# motor_node.net
KiCad netlist of a schematic drawn in EAGLE
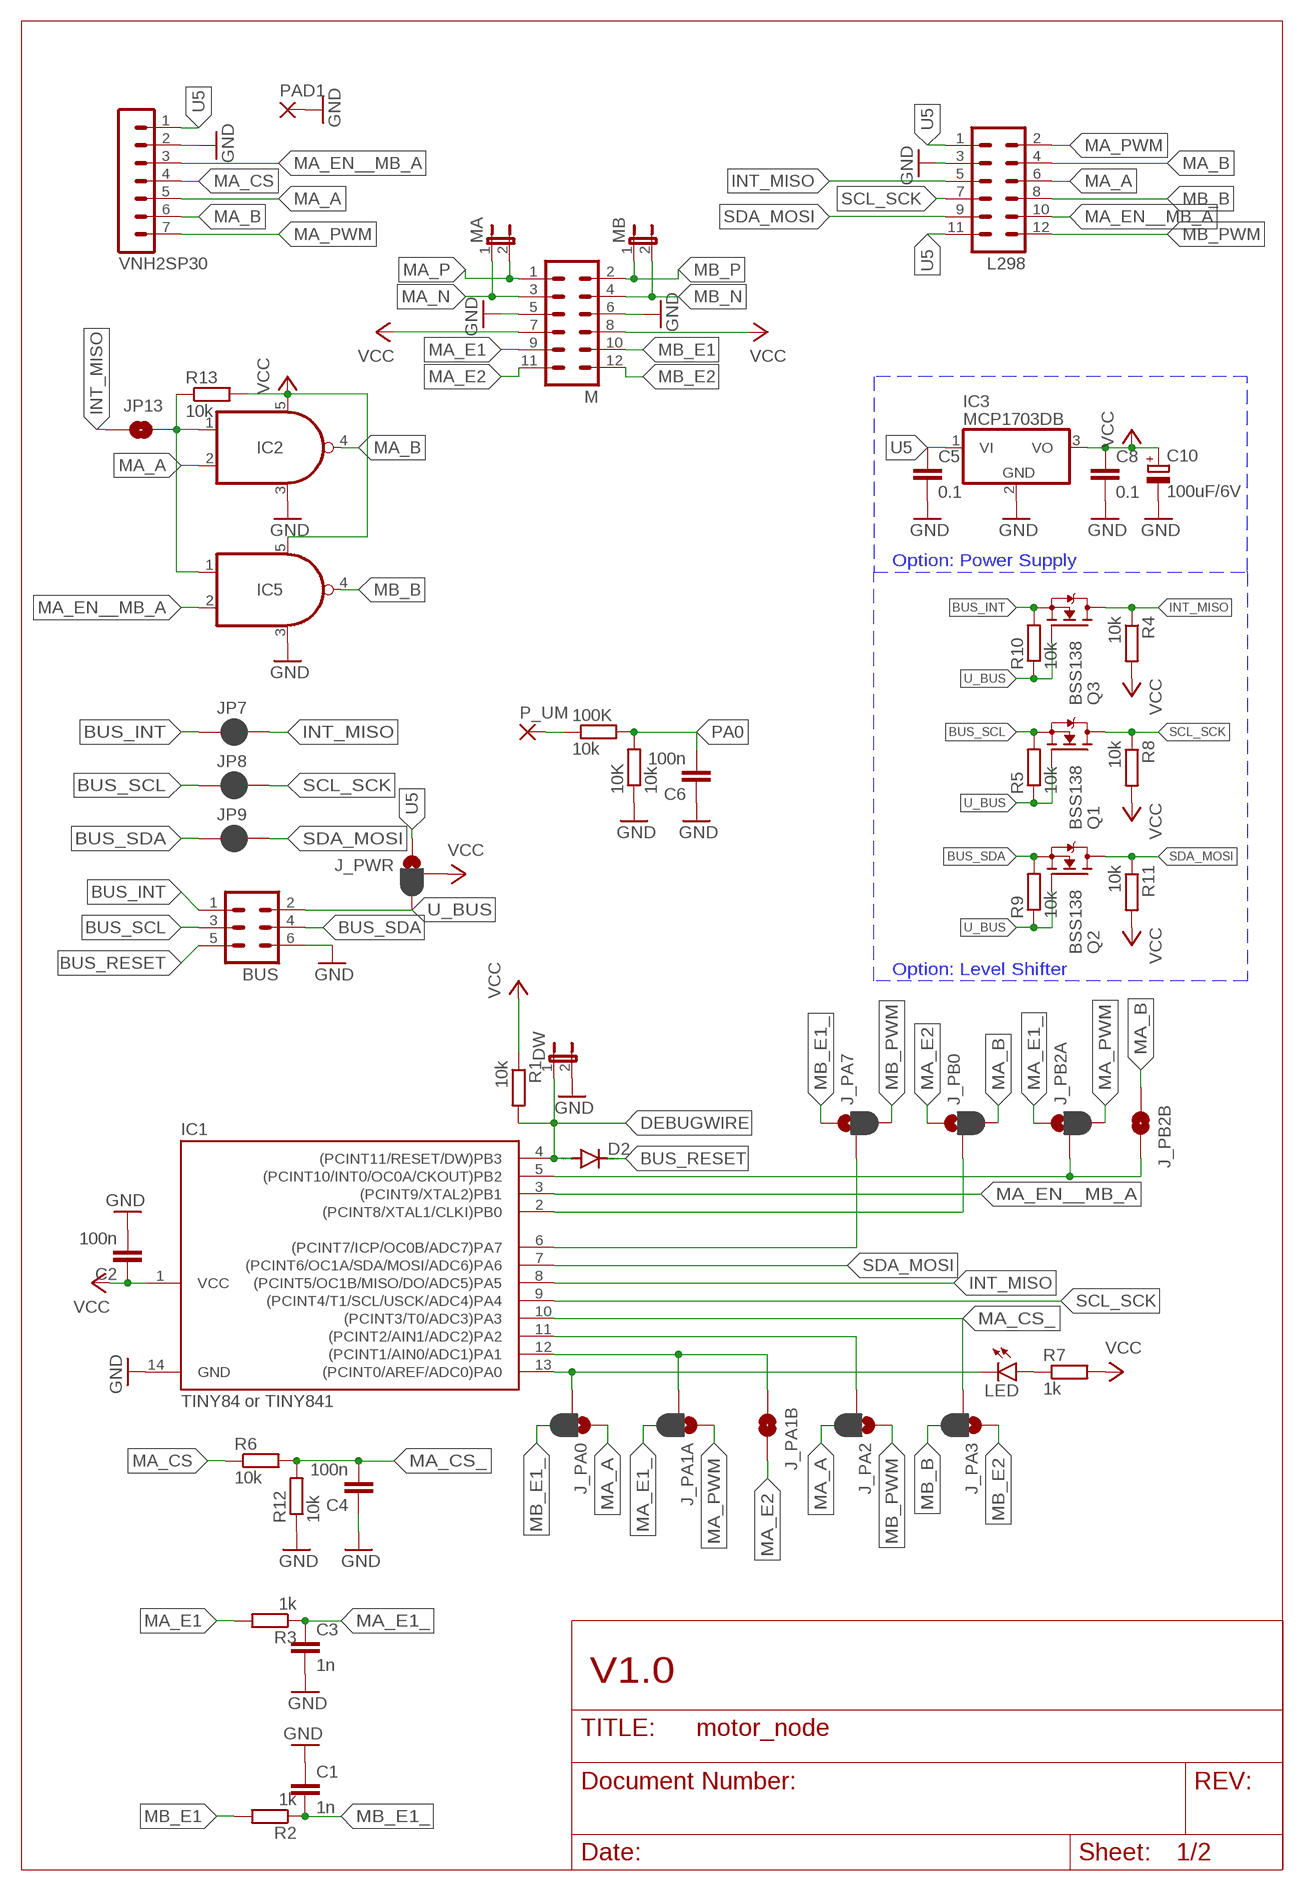
[diagram p0: schematic, sheet 1]

(export (version "E")
  (design (tool "Eeschema 10.0.6"))
  (components
    (comp (ref "10K")
      (value "10k")
      (footprint "eagle-import:M0805")
      (libsource (lib "eagle-import") (part "rcl_334_R-EU_M0805"))
    )
    (comp (ref "100K")
      (value "10k")
      (footprint "eagle-import:M0805")
      (libsource (lib "eagle-import") (part "rcl_334_R-EU_M0805"))
    )
    (comp (ref "BUS")
      (value "ML6")
      (footprint "eagle-import:ML6")
      (libsource (lib "eagle-import") (part "ML6"))
    )
    (comp (ref "C1")
      (value "1n")
      (footprint "eagle-import:C0805")
      (libsource (lib "eagle-import") (part "C-EUC0805"))
    )
    (comp (ref "C2")
      (value "100n")
      (footprint "eagle-import:C0805")
      (libsource (lib "eagle-import") (part "C-EUC0805"))
    )
    (comp (ref "C3")
      (value "1n")
      (footprint "eagle-import:C0805")
      (libsource (lib "eagle-import") (part "C-EUC0805"))
    )
    (comp (ref "C4")
      (value "100n")
      (footprint "eagle-import:C0805")
      (libsource (lib "eagle-import") (part "C-EUC0805"))
    )
    (comp (ref "C5")
      (value "0.1")
      (footprint "eagle-import:C0805")
      (libsource (lib "eagle-import") (part "C-EUC0805"))
    )
    (comp (ref "C6")
      (value "100n")
      (footprint "eagle-import:C0805")
      (libsource (lib "eagle-import") (part "C-EUC0805"))
    )
    (comp (ref "C8")
      (value "0.1")
      (footprint "eagle-import:C0805")
      (libsource (lib "eagle-import") (part "C-EUC0805"))
    )
    (comp (ref "C10")
      (value "100uF/6V")
      (footprint "eagle-import:B_3528-21R")
      (libsource (lib "eagle-import") (part "CPOL-EUB/3528-21R"))
    )
    (comp (ref "D2")
      (value "DIODE-MINIMELF")
      (footprint "eagle-import:MINIMELF")
      (libsource (lib "eagle-import") (part "DIODE-MINIMELF"))
    )
    (comp (ref "DW")
      (value "JP1E")
      (footprint "eagle-import:JP1")
      (libsource (lib "eagle-import") (part "JP1E"))
    )
    (comp (ref "IC1")
      (value "TINY84 or TINY841")
      (footprint "eagle-import:SOIC14")
      (libsource (lib "eagle-import") (part "TINY24/44/84-SSU"))
    )
    (comp (ref "IC2")
      (value "AHC00-DB")
      (footprint "eagle-import:SOT-23_5")
      (libsource (lib "eagle-import") (part "AHC00-DB"))
    )
    (comp (ref "IC3")
      (value "MCP1703DB")
      (footprint "eagle-import:SOT223")
      (libsource (lib "eagle-import") (part "MCP1703DB"))
    )
    (comp (ref "IC5")
      (value "AHC00-DB")
      (footprint "eagle-import:SOT-23_5")
      (libsource (lib "eagle-import") (part "AHC00-DB"))
    )
    (comp (ref "JP7")
      (value "JUMPER-SMT_2_NC_PASTE_NO-SILK")
      (footprint "eagle-import:SMT-JUMPER_2_NC_PASTE_NO-SILK")
      (libsource (lib "eagle-import") (part "JUMPER-SMT_2_NC_PASTE_NO-SILK"))
    )
    (comp (ref "JP8")
      (value "JUMPER-SMT_2_NC_PASTE_NO-SILK")
      (footprint "eagle-import:SMT-JUMPER_2_NC_PASTE_NO-SILK")
      (libsource (lib "eagle-import") (part "JUMPER-SMT_2_NC_PASTE_NO-SILK"))
    )
    (comp (ref "JP9")
      (value "JUMPER-SMT_2_NC_PASTE_NO-SILK")
      (footprint "eagle-import:SMT-JUMPER_2_NC_PASTE_NO-SILK")
      (libsource (lib "eagle-import") (part "JUMPER-SMT_2_NC_PASTE_NO-SILK"))
    )
    (comp (ref "JP13")
      (value "JUMPER-SMT_2_NO_NO-SILK")
      (footprint "eagle-import:SMT-JUMPER_2_NO_NO-SILK")
      (libsource (lib "eagle-import") (part "JUMPER-SMT_2_NO_NO-SILK"))
    )
    (comp (ref "J_PA0")
      (value "JUMPER-SMT_3_1-NC_PASTE_NO-SILK")
      (footprint "eagle-import:SMT-JUMPER_3_1-NC_PASTE_NO-SILK")
      (libsource (lib "eagle-import") (part "JUMPER-SMT_3_1-NC_PASTE_NO-SILK"))
    )
    (comp (ref "J_PA1A")
      (value "JUMPER-SMT_3_1-NC_PASTE_NO-SILK")
      (footprint "eagle-import:SMT-JUMPER_3_1-NC_PASTE_NO-SILK")
      (libsource (lib "eagle-import") (part "JUMPER-SMT_3_1-NC_PASTE_NO-SILK"))
    )
    (comp (ref "J_PA1B")
      (value "JUMPER-SMT_2_NO_NO-SILK")
      (footprint "eagle-import:SMT-JUMPER_2_NO_NO-SILK")
      (libsource (lib "eagle-import") (part "JUMPER-SMT_2_NO_NO-SILK"))
    )
    (comp (ref "J_PA2")
      (value "JUMPER-SMT_3_1-NC_PASTE_NO-SILK")
      (footprint "eagle-import:SMT-JUMPER_3_1-NC_PASTE_NO-SILK")
      (libsource (lib "eagle-import") (part "JUMPER-SMT_3_1-NC_PASTE_NO-SILK"))
    )
    (comp (ref "J_PA3")
      (value "JUMPER-SMT_3_1-NC_PASTE_NO-SILK")
      (footprint "eagle-import:SMT-JUMPER_3_1-NC_PASTE_NO-SILK")
      (libsource (lib "eagle-import") (part "JUMPER-SMT_3_1-NC_PASTE_NO-SILK"))
    )
    (comp (ref "J_PA7")
      (value "JUMPER-SMT_3_1-NC_PASTE_NO-SILK")
      (footprint "eagle-import:SMT-JUMPER_3_1-NC_PASTE_NO-SILK")
      (libsource (lib "eagle-import") (part "JUMPER-SMT_3_1-NC_PASTE_NO-SILK"))
    )
    (comp (ref "J_PB0")
      (value "JUMPER-SMT_3_1-NC_PASTE_NO-SILK")
      (footprint "eagle-import:SMT-JUMPER_3_1-NC_PASTE_NO-SILK")
      (libsource (lib "eagle-import") (part "JUMPER-SMT_3_1-NC_PASTE_NO-SILK"))
    )
    (comp (ref "J_PB2A")
      (value "JUMPER-SMT_3_1-NC_PASTE_NO-SILK")
      (footprint "eagle-import:SMT-JUMPER_3_1-NC_PASTE_NO-SILK")
      (libsource (lib "eagle-import") (part "JUMPER-SMT_3_1-NC_PASTE_NO-SILK"))
    )
    (comp (ref "J_PB2B")
      (value "JUMPER-SMT_2_NO_NO-SILK")
      (footprint "eagle-import:SMT-JUMPER_2_NO_NO-SILK")
      (libsource (lib "eagle-import") (part "JUMPER-SMT_2_NO_NO-SILK"))
    )
    (comp (ref "J_PWR")
      (value "JUMPER-SMT_3_1-NC_PASTE_NO-SILK")
      (footprint "eagle-import:SMT-JUMPER_3_1-NC_PASTE_NO-SILK")
      (libsource (lib "eagle-import") (part "JUMPER-SMT_3_1-NC_PASTE_NO-SILK"))
    )
    (comp (ref "L298")
      (value "MA06-2")
      (footprint "eagle-import:MA06-2")
      (libsource (lib "eagle-import") (part "MA06-2"))
    )
    (comp (ref "LED")
      (value "LEDCHIPLED_0805")
      (footprint "eagle-import:CHIPLED_0805")
      (libsource (lib "eagle-import") (part "LEDCHIPLED_0805"))
    )
    (comp (ref "M")
      (value "MA06-2")
      (footprint "eagle-import:MA06-2")
      (libsource (lib "eagle-import") (part "MA06-2"))
    )
    (comp (ref "MA")
      (value "JP1E")
      (footprint "eagle-import:JP1")
      (libsource (lib "eagle-import") (part "JP1E"))
    )
    (comp (ref "MB")
      (value "JP1E")
      (footprint "eagle-import:JP1")
      (libsource (lib "eagle-import") (part "JP1E"))
    )
    (comp (ref "PAD1")
      (value "2,54/0,8")
      (footprint "eagle-import:2,54_0,8")
      (libsource (lib "eagle-import") (part "2,54/0,8"))
    )
    (comp (ref "P_UM")
      (value "1,6/0,8")
      (footprint "eagle-import:1,6_0,8")
      (libsource (lib "eagle-import") (part "1,6/0,8"))
    )
    (comp (ref "Q1")
      (value "BSS138")
      (footprint "eagle-import:SOT23")
      (fields (field (name "MF") "Fairchild"))
      (libsource (lib "eagle-import") (part "BSS138"))
    )
    (comp (ref "Q2")
      (value "BSS138")
      (footprint "eagle-import:SOT23")
      (fields (field (name "MF") "Fairchild"))
      (libsource (lib "eagle-import") (part "BSS138"))
    )
    (comp (ref "Q3")
      (value "BSS138")
      (footprint "eagle-import:SOT23")
      (fields (field (name "MF") "Fairchild"))
      (libsource (lib "eagle-import") (part "BSS138"))
    )
    (comp (ref "R1")
      (value "10k")
      (footprint "eagle-import:M0805")
      (libsource (lib "eagle-import") (part "rcl_334_R-EU_M0805"))
    )
    (comp (ref "R2")
      (value "1k")
      (footprint "eagle-import:M0805")
      (libsource (lib "eagle-import") (part "rcl_334_R-EU_M0805"))
    )
    (comp (ref "R3")
      (value "1k")
      (footprint "eagle-import:M0805")
      (libsource (lib "eagle-import") (part "rcl_334_R-EU_M0805"))
    )
    (comp (ref "R4")
      (value "10k")
      (footprint "eagle-import:M0805")
      (libsource (lib "eagle-import") (part "rcl_334_R-EU_M0805"))
    )
    (comp (ref "R5")
      (value "10k")
      (footprint "eagle-import:R0805")
      (libsource (lib "eagle-import") (part "R-EU_R0805"))
    )
    (comp (ref "R6")
      (value "10k")
      (footprint "eagle-import:M0805")
      (libsource (lib "eagle-import") (part "rcl_334_R-EU_M0805"))
    )
    (comp (ref "R7")
      (value "1k")
      (footprint "eagle-import:R0603")
      (libsource (lib "eagle-import") (part "rcl_334_R-EU_R0603"))
    )
    (comp (ref "R8")
      (value "10k")
      (footprint "eagle-import:M0805")
      (libsource (lib "eagle-import") (part "rcl_334_R-EU_M0805"))
    )
    (comp (ref "R9")
      (value "10k")
      (footprint "eagle-import:R0805")
      (libsource (lib "eagle-import") (part "R-EU_R0805"))
    )
    (comp (ref "R10")
      (value "10k")
      (footprint "eagle-import:R0805")
      (libsource (lib "eagle-import") (part "R-EU_R0805"))
    )
    (comp (ref "R11")
      (value "10k")
      (footprint "eagle-import:M0805")
      (libsource (lib "eagle-import") (part "rcl_334_R-EU_M0805"))
    )
    (comp (ref "R12")
      (value "10k")
      (footprint "eagle-import:M0805")
      (libsource (lib "eagle-import") (part "rcl_334_R-EU_M0805"))
    )
    (comp (ref "R13")
      (value "10k")
      (footprint "eagle-import:R0805")
      (libsource (lib "eagle-import") (part "R-EU_R0805"))
    )
    (comp (ref "VNH2SP30")
      (value "MA07-1")
      (footprint "eagle-import:MA07-1")
      (libsource (lib "eagle-import") (part "MA07-1"))
    )
  )
  (nets
    (net (code "1") (name "BUS_INT") (class "Default")
      (node (ref "BUS") (pin "1") (pinfunction "1_1") (pintype "passive"))
      (node (ref "JP7") (pin "1") (pinfunction "1_1") (pintype "passive"))
      (node (ref "Q3") (pin "2") (pinfunction "S_2") (pintype "passive"))
      (node (ref "R10") (pin "2") (pinfunction "2_2") (pintype "passive"))
    )
    (net (code "2") (name "BUS_RESET") (class "Default")
      (node (ref "BUS") (pin "5") (pinfunction "5_5") (pintype "passive"))
      (node (ref "D2") (pin "C") (pinfunction "C_C") (pintype "passive"))
    )
    (net (code "3") (name "BUS_SCL") (class "Default")
      (node (ref "BUS") (pin "3") (pinfunction "3_3") (pintype "passive"))
      (node (ref "JP8") (pin "1") (pinfunction "1_1") (pintype "passive"))
      (node (ref "Q1") (pin "2") (pinfunction "S_2") (pintype "passive"))
      (node (ref "R5") (pin "2") (pinfunction "2_2") (pintype "passive"))
    )
    (net (code "4") (name "BUS_SDA") (class "Default")
      (node (ref "BUS") (pin "4") (pinfunction "4_4") (pintype "passive"))
      (node (ref "JP9") (pin "1") (pinfunction "1_1") (pintype "passive"))
      (node (ref "Q2") (pin "2") (pinfunction "S_2") (pintype "passive"))
      (node (ref "R9") (pin "2") (pinfunction "2_2") (pintype "passive"))
    )
    (net (code "5") (name "DEBUGWIRE") (class "Default")
      (node (ref "D2") (pin "A") (pinfunction "A_A") (pintype "passive"))
      (node (ref "DW") (pin "1") (pinfunction "1_1") (pintype "passive"))
      (node (ref "IC1") (pin "4") (pinfunction "(PCINT11/RESET/DW)PB3_4") (pintype "bidirectional"))
      (node (ref "R1") (pin "2") (pinfunction "2_2") (pintype "passive"))
    )
    (net (code "6") (name "GND") (class "Default")
      (node (ref "10K") (pin "1") (pinfunction "1_1") (pintype "passive"))
      (node (ref "BUS") (pin "6") (pinfunction "6_6") (pintype "passive"))
      (node (ref "C1") (pin "1") (pinfunction "1_1") (pintype "passive"))
      (node (ref "C10") (pin "-") (pinfunction "-_-") (pintype "passive"))
      (node (ref "C2") (pin "2") (pinfunction "2_2") (pintype "passive"))
      (node (ref "C3") (pin "2") (pinfunction "2_2") (pintype "passive"))
      (node (ref "C4") (pin "1") (pinfunction "1_1") (pintype "passive"))
      (node (ref "C5") (pin "2") (pinfunction "2_2") (pintype "passive"))
      (node (ref "C6") (pin "1") (pinfunction "1_1") (pintype "passive"))
      (node (ref "C8") (pin "2") (pinfunction "2_2") (pintype "passive"))
      (node (ref "DW") (pin "2") (pinfunction "2_2") (pintype "passive"))
      (node (ref "IC1") (pin "14") (pinfunction "GND_14") (pintype "power_in"))
      (node (ref "IC2") (pin "3") (pinfunction "GND_3") (pintype "power_in"))
      (node (ref "IC3") (pin "2") (pinfunction "GND_2") (pintype "passive"))
      (node (ref "IC5") (pin "3") (pinfunction "GND_3") (pintype "power_in"))
      (node (ref "L298") (pin "3") (pinfunction "3_3") (pintype "passive"))
      (node (ref "M") (pin "5") (pinfunction "5_5") (pintype "passive"))
      (node (ref "M") (pin "6") (pinfunction "6_6") (pintype "passive"))
      (node (ref "PAD1") (pin "1") (pinfunction "P_1") (pintype "passive"))
      (node (ref "R12") (pin "1") (pinfunction "1_1") (pintype "passive"))
      (node (ref "VNH2SP30") (pin "2") (pinfunction "2_2") (pintype "passive"))
    )
    (net (code "7") (name "INT_MISO") (class "Default")
      (node (ref "IC1") (pin "8") (pinfunction "(PCINT5/OC1B/MISO/DO/ADC5)PA5_8") (pintype "bidirectional"))
      (node (ref "JP13") (pin "1") (pinfunction "1_1") (pintype "passive"))
      (node (ref "JP7") (pin "2") (pinfunction "2_2") (pintype "passive"))
      (node (ref "L298") (pin "5") (pinfunction "5_5") (pintype "passive"))
      (node (ref "Q3") (pin "3") (pinfunction "D_3") (pintype "passive"))
      (node (ref "R4") (pin "1") (pinfunction "1_1") (pintype "passive"))
    )
    (net (code "8") (name "MA_A") (class "Default")
      (node (ref "IC2") (pin "2") (pinfunction "I1_2") (pintype "input"))
      (node (ref "J_PA0") (pin "1") (pinfunction "1_1") (pintype "passive"))
      (node (ref "J_PA2") (pin "3") (pinfunction "3_3") (pintype "passive"))
      (node (ref "L298") (pin "6") (pinfunction "6_6") (pintype "passive"))
      (node (ref "VNH2SP30") (pin "5") (pinfunction "5_5") (pintype "passive"))
    )
    (net (code "9") (name "MA_B") (class "Default")
      (node (ref "IC2") (pin "4") (pinfunction "O_4") (pintype "output"))
      (node (ref "J_PB0") (pin "3") (pinfunction "3_3") (pintype "passive"))
      (node (ref "J_PB2B") (pin "1") (pinfunction "1_1") (pintype "passive"))
      (node (ref "L298") (pin "4") (pinfunction "4_4") (pintype "passive"))
      (node (ref "VNH2SP30") (pin "6") (pinfunction "6_6") (pintype "passive"))
    )
    (net (code "10") (name "MA_CS") (class "Default")
      (node (ref "R6") (pin "1") (pinfunction "1_1") (pintype "passive"))
      (node (ref "VNH2SP30") (pin "4") (pinfunction "4_4") (pintype "passive"))
    )
    (net (code "11") (name "MA_CS_") (class "Default")
      (node (ref "C4") (pin "2") (pinfunction "2_2") (pintype "passive"))
      (node (ref "IC1") (pin "10") (pinfunction "(PCINT3/T0/ADC3)PA3_10") (pintype "bidirectional"))
      (node (ref "J_PA3") (pin "2") (pinfunction "2_2") (pintype "passive"))
      (node (ref "R12") (pin "2") (pinfunction "2_2") (pintype "passive"))
      (node (ref "R6") (pin "2") (pinfunction "2_2") (pintype "passive"))
    )
    (net (code "12") (name "MA_E1") (class "Default")
      (node (ref "M") (pin "9") (pinfunction "9_9") (pintype "passive"))
      (node (ref "R3") (pin "2") (pinfunction "2_2") (pintype "passive"))
    )
    (net (code "13") (name "MA_E1_") (class "Default")
      (node (ref "C3") (pin "1") (pinfunction "1_1") (pintype "passive"))
      (node (ref "J_PA1A") (pin "3") (pinfunction "3_3") (pintype "passive"))
      (node (ref "J_PB2A") (pin "1") (pinfunction "1_1") (pintype "passive"))
      (node (ref "R3") (pin "1") (pinfunction "1_1") (pintype "passive"))
    )
    (net (code "14") (name "MA_E2") (class "Default")
      (node (ref "J_PA1B") (pin "2") (pinfunction "2_2") (pintype "passive"))
      (node (ref "J_PB0") (pin "1") (pinfunction "1_1") (pintype "passive"))
      (node (ref "M") (pin "11") (pinfunction "11_11") (pintype "passive"))
    )
    (net (code "15") (name "MA_EN__MB_A") (class "Default")
      (node (ref "IC1") (pin "3") (pinfunction "(PCINT9/XTAL2)PB1_3") (pintype "bidirectional"))
      (node (ref "IC5") (pin "2") (pinfunction "I1_2") (pintype "input"))
      (node (ref "L298") (pin "10") (pinfunction "10_10") (pintype "passive"))
      (node (ref "VNH2SP30") (pin "3") (pinfunction "3_3") (pintype "passive"))
    )
    (net (code "16") (name "MA_N") (class "Default")
      (node (ref "M") (pin "3") (pinfunction "3_3") (pintype "passive"))
      (node (ref "MA") (pin "1") (pinfunction "1_1") (pintype "passive"))
    )
    (net (code "17") (name "MA_P") (class "Default")
      (node (ref "M") (pin "1") (pinfunction "1_1") (pintype "passive"))
      (node (ref "MA") (pin "2") (pinfunction "2_2") (pintype "passive"))
    )
    (net (code "18") (name "MA_PWM") (class "Default")
      (node (ref "J_PA1A") (pin "1") (pinfunction "1_1") (pintype "passive"))
      (node (ref "J_PB2A") (pin "3") (pinfunction "3_3") (pintype "passive"))
      (node (ref "L298") (pin "2") (pinfunction "2_2") (pintype "passive"))
      (node (ref "VNH2SP30") (pin "7") (pinfunction "7_7") (pintype "passive"))
    )
    (net (code "19") (name "MB_B") (class "Default")
      (node (ref "IC5") (pin "4") (pinfunction "O_4") (pintype "output"))
      (node (ref "J_PA3") (pin "3") (pinfunction "3_3") (pintype "passive"))
      (node (ref "L298") (pin "8") (pinfunction "8_8") (pintype "passive"))
    )
    (net (code "20") (name "MB_E1") (class "Default")
      (node (ref "M") (pin "10") (pinfunction "10_10") (pintype "passive"))
      (node (ref "R2") (pin "2") (pinfunction "2_2") (pintype "passive"))
    )
    (net (code "21") (name "MB_E1_") (class "Default")
      (node (ref "C1") (pin "2") (pinfunction "2_2") (pintype "passive"))
      (node (ref "J_PA0") (pin "3") (pinfunction "3_3") (pintype "passive"))
      (node (ref "J_PA7") (pin "1") (pinfunction "1_1") (pintype "passive"))
      (node (ref "R2") (pin "1") (pinfunction "1_1") (pintype "passive"))
    )
    (net (code "22") (name "MB_E2") (class "Default")
      (node (ref "J_PA3") (pin "1") (pinfunction "1_1") (pintype "passive"))
      (node (ref "M") (pin "12") (pinfunction "12_12") (pintype "passive"))
    )
    (net (code "23") (name "MB_N") (class "Default")
      (node (ref "M") (pin "4") (pinfunction "4_4") (pintype "passive"))
      (node (ref "MB") (pin "2") (pinfunction "2_2") (pintype "passive"))
    )
    (net (code "24") (name "MB_P") (class "Default")
      (node (ref "M") (pin "2") (pinfunction "2_2") (pintype "passive"))
      (node (ref "MB") (pin "1") (pinfunction "1_1") (pintype "passive"))
    )
    (net (code "25") (name "MB_PWM") (class "Default")
      (node (ref "J_PA2") (pin "1") (pinfunction "1_1") (pintype "passive"))
      (node (ref "J_PA7") (pin "3") (pinfunction "3_3") (pintype "passive"))
      (node (ref "L298") (pin "12") (pinfunction "12_12") (pintype "passive"))
    )
    (net (code "26") (name "Net-(IC1-(PCINT1{slash}AIN0{slash}ADC1)PA1)") (class "Default")
      (node (ref "IC1") (pin "12") (pinfunction "(PCINT1/AIN0/ADC1)PA1_12") (pintype "bidirectional"))
      (node (ref "J_PA1A") (pin "2") (pinfunction "2_2") (pintype "passive"))
      (node (ref "J_PA1B") (pin "1") (pinfunction "1_1") (pintype "passive"))
    )
    (net (code "27") (name "Net-(IC1-(PCINT2{slash}AIN1{slash}ADC2)PA2)") (class "Default")
      (node (ref "IC1") (pin "11") (pinfunction "(PCINT2/AIN1/ADC2)PA2_11") (pintype "bidirectional"))
      (node (ref "J_PA2") (pin "2") (pinfunction "2_2") (pintype "passive"))
    )
    (net (code "28") (name "Net-(IC1-(PCINT7{slash}ICP{slash}OC0B{slash}ADC7)PA7)") (class "Default")
      (node (ref "IC1") (pin "6") (pinfunction "(PCINT7/ICP/OC0B/ADC7)PA7_6") (pintype "bidirectional"))
      (node (ref "J_PA7") (pin "2") (pinfunction "2_2") (pintype "passive"))
    )
    (net (code "29") (name "Net-(IC1-(PCINT8{slash}XTAL1{slash}CLKI)PB0)") (class "Default")
      (node (ref "IC1") (pin "2") (pinfunction "(PCINT8/XTAL1/CLKI)PB0_2") (pintype "bidirectional"))
      (node (ref "J_PB0") (pin "2") (pinfunction "2_2") (pintype "passive"))
    )
    (net (code "30") (name "Net-(IC1-(PCINT10{slash}INT0{slash}OC0A{slash}CKOUT)PB2)") (class "Default")
      (node (ref "IC1") (pin "5") (pinfunction "(PCINT10/INT0/OC0A/CKOUT)PB2_5") (pintype "bidirectional"))
      (node (ref "J_PB2A") (pin "2") (pinfunction "2_2") (pintype "passive"))
      (node (ref "J_PB2B") (pin "2") (pinfunction "2_2") (pintype "passive"))
    )
    (net (code "31") (name "Net-(IC2-I0)") (class "Default")
      (node (ref "IC2") (pin "1") (pinfunction "I0_1") (pintype "input"))
      (node (ref "IC5") (pin "1") (pinfunction "I0_1") (pintype "input"))
      (node (ref "JP13") (pin "2") (pinfunction "2_2") (pintype "passive"))
      (node (ref "R13") (pin "1") (pinfunction "1_1") (pintype "passive"))
    )
    (net (code "32") (name "Net-(LED-PadA)") (class "Default")
      (node (ref "LED") (pin "A") (pinfunction "A_A") (pintype "passive"))
      (node (ref "R7") (pin "1") (pinfunction "1_1") (pintype "passive"))
    )
    (net (code "33") (name "Net-(P_UM-P)") (class "Default")
      (node (ref "100K") (pin "1") (pinfunction "1_1") (pintype "passive"))
      (node (ref "P_UM") (pin "1") (pinfunction "P_1") (pintype "passive"))
    )
    (net (code "34") (name "PA0") (class "Default")
      (node (ref "100K") (pin "2") (pinfunction "2_2") (pintype "passive"))
      (node (ref "10K") (pin "2") (pinfunction "2_2") (pintype "passive"))
      (node (ref "C6") (pin "2") (pinfunction "2_2") (pintype "passive"))
      (node (ref "IC1") (pin "13") (pinfunction "(PCINT0/AREF/ADC0)PA0_13") (pintype "bidirectional"))
      (node (ref "J_PA0") (pin "2") (pinfunction "2_2") (pintype "passive"))
      (node (ref "LED") (pin "C") (pinfunction "C_C") (pintype "passive"))
    )
    (net (code "35") (name "SCL_SCK") (class "Default")
      (node (ref "IC1") (pin "9") (pinfunction "(PCINT4/T1/SCL/USCK/ADC4)PA4_9") (pintype "bidirectional"))
      (node (ref "JP8") (pin "2") (pinfunction "2_2") (pintype "passive"))
      (node (ref "L298") (pin "7") (pinfunction "7_7") (pintype "passive"))
      (node (ref "Q1") (pin "3") (pinfunction "D_3") (pintype "passive"))
      (node (ref "R8") (pin "1") (pinfunction "1_1") (pintype "passive"))
    )
    (net (code "36") (name "SDA_MOSI") (class "Default")
      (node (ref "IC1") (pin "7") (pinfunction "(PCINT6/OC1A/SDA/MOSI/ADC6)PA6_7") (pintype "bidirectional"))
      (node (ref "JP9") (pin "2") (pinfunction "2_2") (pintype "passive"))
      (node (ref "L298") (pin "9") (pinfunction "9_9") (pintype "passive"))
      (node (ref "Q2") (pin "3") (pinfunction "D_3") (pintype "passive"))
      (node (ref "R11") (pin "1") (pinfunction "1_1") (pintype "passive"))
    )
    (net (code "37") (name "U5") (class "Default")
      (node (ref "C5") (pin "1") (pinfunction "1_1") (pintype "passive"))
      (node (ref "IC3") (pin "1") (pinfunction "VI_1") (pintype "input"))
      (node (ref "J_PWR") (pin "1") (pinfunction "1_1") (pintype "passive"))
      (node (ref "L298") (pin "1") (pinfunction "1_1") (pintype "passive"))
      (node (ref "L298") (pin "11") (pinfunction "11_11") (pintype "passive"))
      (node (ref "VNH2SP30") (pin "1") (pinfunction "1_1") (pintype "passive"))
    )
    (net (code "38") (name "U_BUS") (class "Default")
      (node (ref "BUS") (pin "2") (pinfunction "2_2") (pintype "passive"))
      (node (ref "J_PWR") (pin "3") (pinfunction "3_3") (pintype "passive"))
      (node (ref "Q1") (pin "1") (pinfunction "G_1") (pintype "passive"))
      (node (ref "Q2") (pin "1") (pinfunction "G_1") (pintype "passive"))
      (node (ref "Q3") (pin "1") (pinfunction "G_1") (pintype "passive"))
      (node (ref "R10") (pin "1") (pinfunction "1_1") (pintype "passive"))
      (node (ref "R5") (pin "1") (pinfunction "1_1") (pintype "passive"))
      (node (ref "R9") (pin "1") (pinfunction "1_1") (pintype "passive"))
    )
    (net (code "39") (name "VCC") (class "Default")
      (node (ref "C10") (pin "+") (pinfunction "+_+") (pintype "passive"))
      (node (ref "C2") (pin "1") (pinfunction "1_1") (pintype "passive"))
      (node (ref "C8") (pin "1") (pinfunction "1_1") (pintype "passive"))
      (node (ref "IC1") (pin "1") (pinfunction "VCC_1") (pintype "power_in"))
      (node (ref "IC2") (pin "5") (pinfunction "VDD_5") (pintype "power_in"))
      (node (ref "IC3") (pin "3") (pinfunction "VO_3") (pintype "passive"))
      (node (ref "IC5") (pin "5") (pinfunction "VDD_5") (pintype "power_in"))
      (node (ref "J_PWR") (pin "2") (pinfunction "2_2") (pintype "passive"))
      (node (ref "M") (pin "7") (pinfunction "7_7") (pintype "passive"))
      (node (ref "M") (pin "8") (pinfunction "8_8") (pintype "passive"))
      (node (ref "R1") (pin "1") (pinfunction "1_1") (pintype "passive"))
      (node (ref "R11") (pin "2") (pinfunction "2_2") (pintype "passive"))
      (node (ref "R13") (pin "2") (pinfunction "2_2") (pintype "passive"))
      (node (ref "R4") (pin "2") (pinfunction "2_2") (pintype "passive"))
      (node (ref "R7") (pin "2") (pinfunction "2_2") (pintype "passive"))
      (node (ref "R8") (pin "2") (pinfunction "2_2") (pintype "passive"))
    )
  )
)
